# Charger.net
KiCad netlist of a schematic drawn in EAGLE
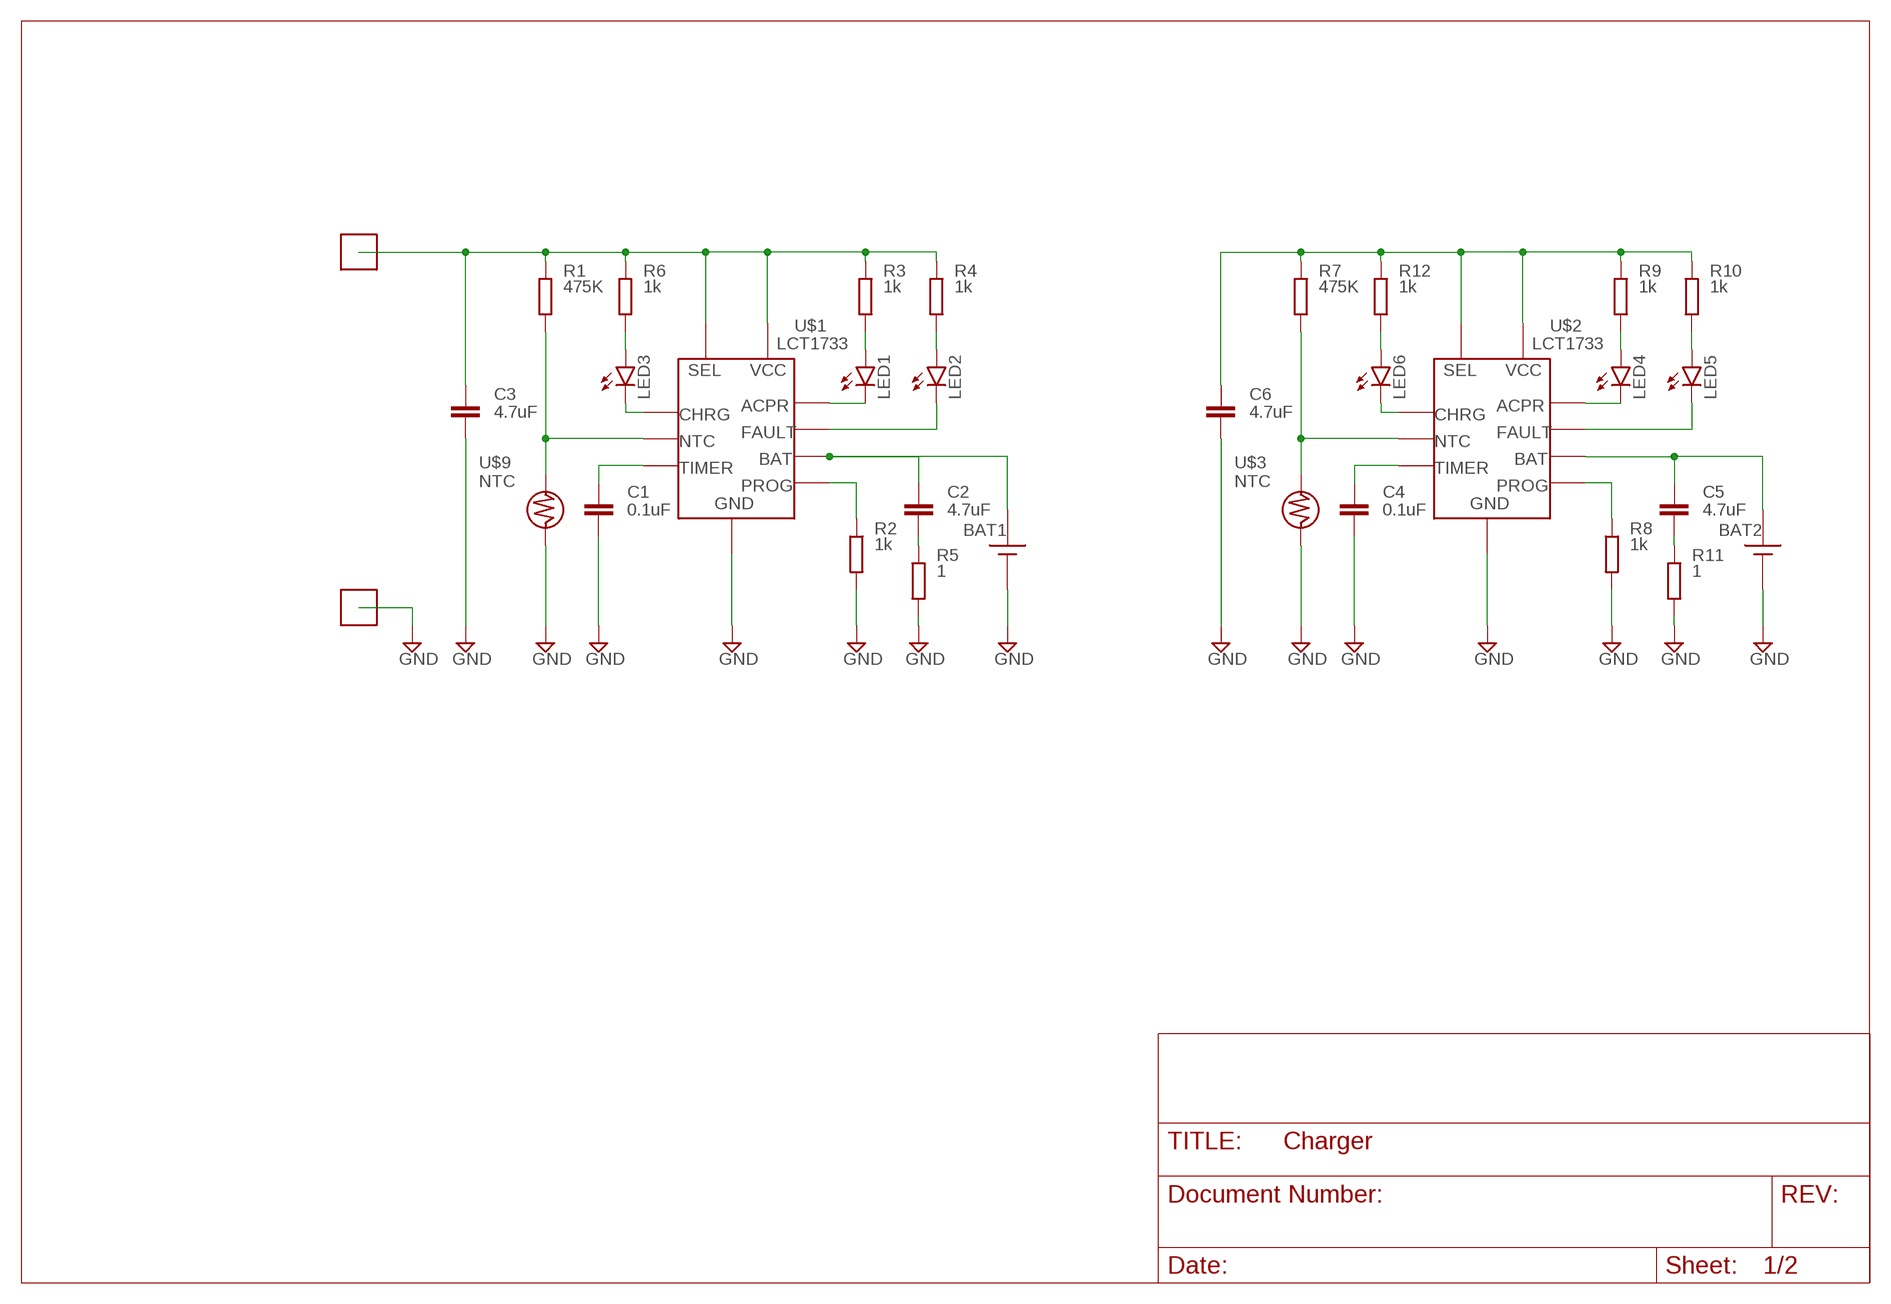
[diagram p0: schematic, sheet 1]
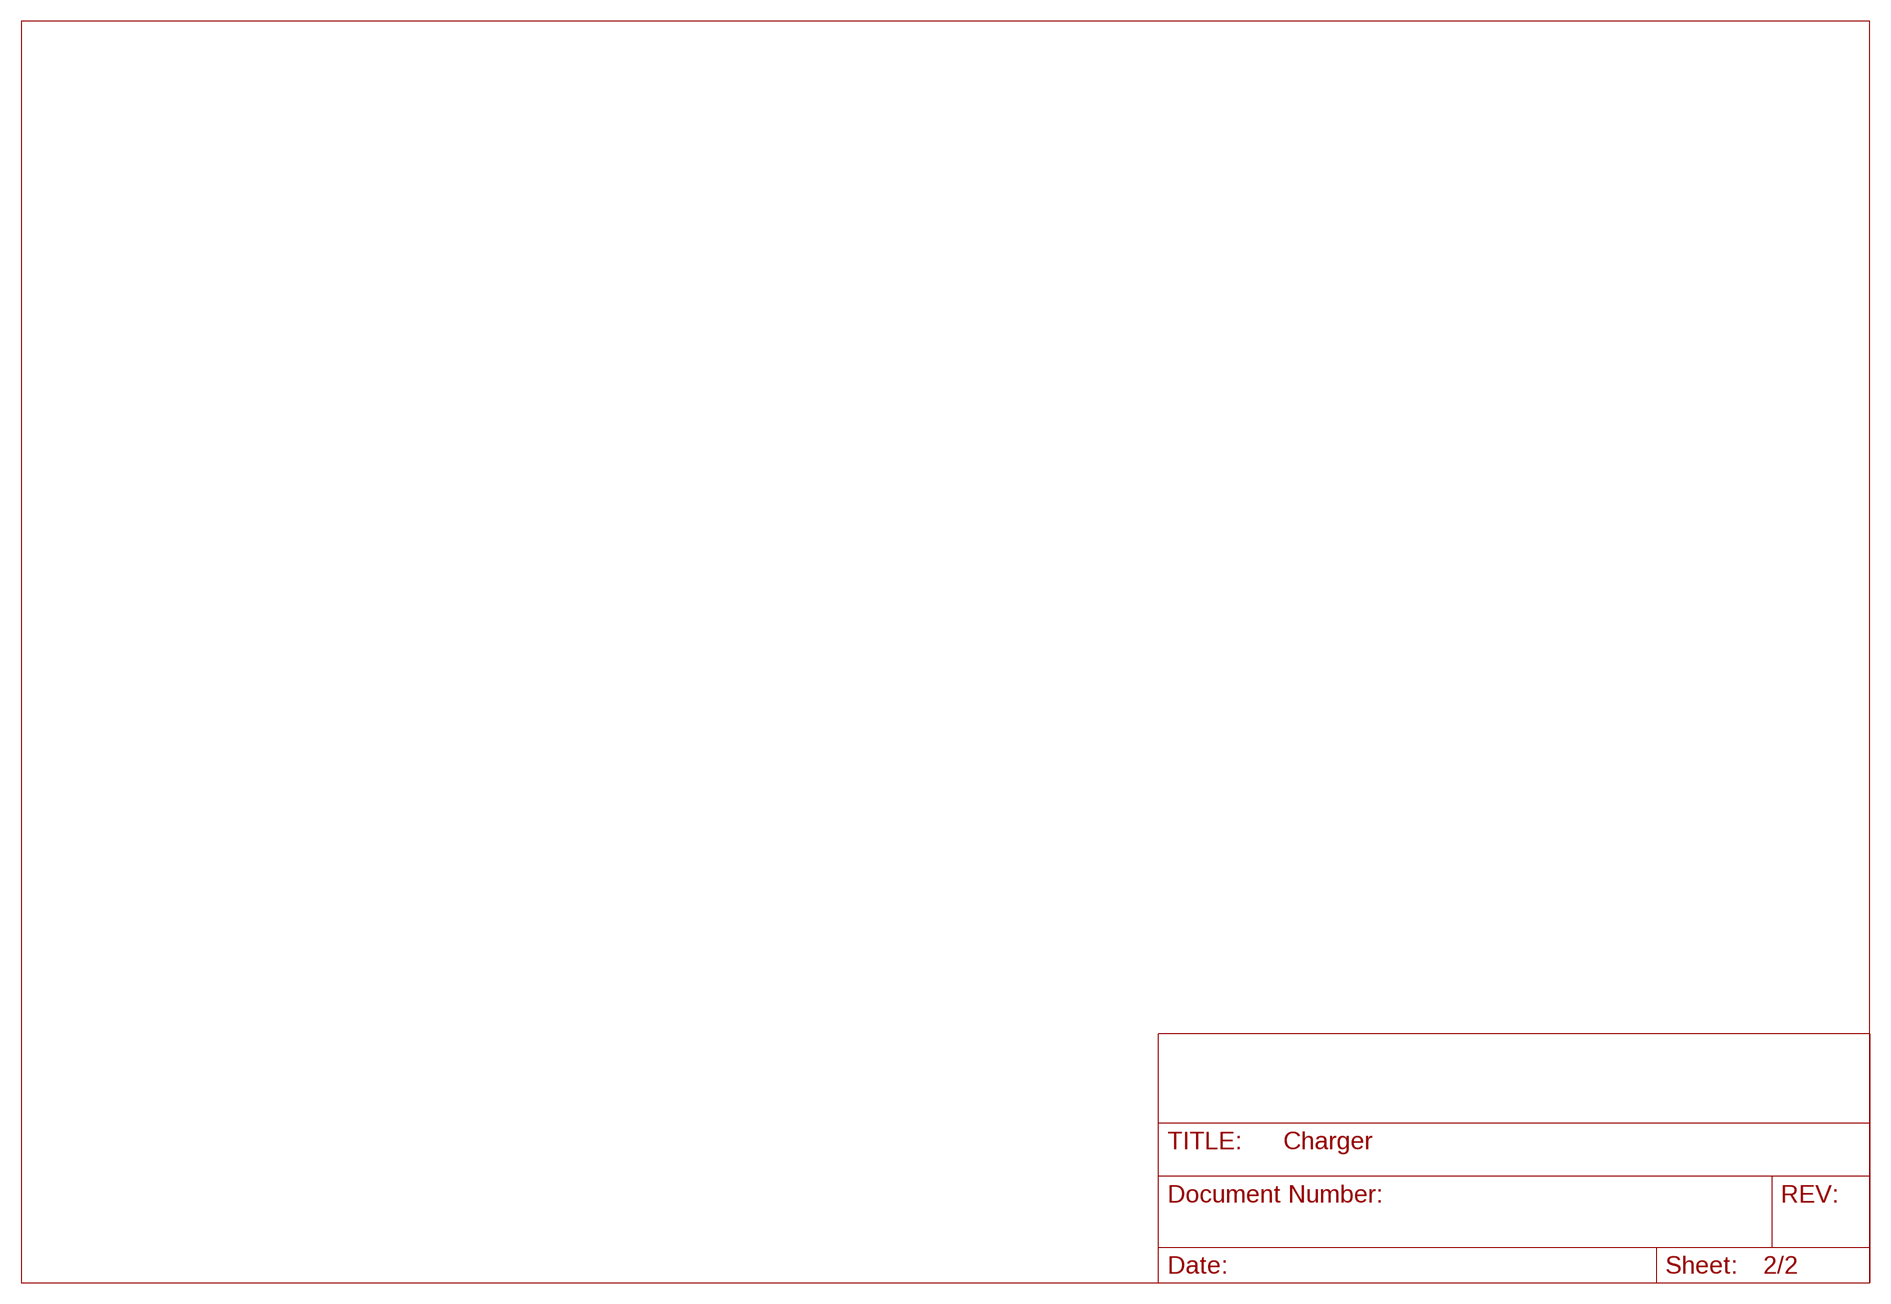
[diagram p1: schematic, sheet 2]

(export (version "E")
  (design (tool "Eeschema 10.0.6"))
  (components
    (comp (ref "BAT1")
      (value "BATBAT")
      (footprint "eagle-import:BAT2")
      (libsource (lib "eagle-import") (part "BATBAT"))
    )
    (comp (ref "BAT2")
      (value "BAT")
      (footprint "eagle-import:BAT")
      (libsource (lib "eagle-import") (part "BAT"))
    )
    (comp (ref "C1")
      (value "0.1uF")
      (footprint "eagle-import:C0603")
      (libsource (lib "eagle-import") (part "C-EUC0603"))
    )
    (comp (ref "C2")
      (value "4.7uF")
      (footprint "eagle-import:C0603")
      (libsource (lib "eagle-import") (part "C-EUC0603"))
    )
    (comp (ref "C3")
      (value "4.7uF")
      (footprint "eagle-import:C0603")
      (libsource (lib "eagle-import") (part "C-EUC0603"))
    )
    (comp (ref "C4")
      (value "0.1uF")
      (footprint "eagle-import:C0603")
      (libsource (lib "eagle-import") (part "C-EUC0603"))
    )
    (comp (ref "C5")
      (value "4.7uF")
      (footprint "eagle-import:C0603")
      (libsource (lib "eagle-import") (part "C-EUC0603"))
    )
    (comp (ref "C6")
      (value "4.7uF")
      (footprint "eagle-import:C0603")
      (libsource (lib "eagle-import") (part "C-EUC0603"))
    )
    (comp (ref "LED1")
      (value "LEDSML0603")
      (footprint "eagle-import:SML0603")
      (libsource (lib "eagle-import") (part "LEDSML0603"))
    )
    (comp (ref "LED2")
      (value "LEDSML0603")
      (footprint "eagle-import:SML0603")
      (libsource (lib "eagle-import") (part "LEDSML0603"))
    )
    (comp (ref "LED3")
      (value "LEDSML0603")
      (footprint "eagle-import:SML0603")
      (libsource (lib "eagle-import") (part "LEDSML0603"))
    )
    (comp (ref "LED4")
      (value "LEDSML0603")
      (footprint "eagle-import:SML0603")
      (libsource (lib "eagle-import") (part "LEDSML0603"))
    )
    (comp (ref "LED5")
      (value "LEDSML0603")
      (footprint "eagle-import:SML0603")
      (libsource (lib "eagle-import") (part "LEDSML0603"))
    )
    (comp (ref "LED6")
      (value "LEDSML0603")
      (footprint "eagle-import:SML0603")
      (libsource (lib "eagle-import") (part "LEDSML0603"))
    )
    (comp (ref "R1")
      (value "475K")
      (footprint "eagle-import:R0603")
      (libsource (lib "eagle-import") (part "R-EU_R0603"))
    )
    (comp (ref "R2")
      (value "1k")
      (footprint "eagle-import:R0603")
      (libsource (lib "eagle-import") (part "R-EU_R0603"))
    )
    (comp (ref "R3")
      (value "1k")
      (footprint "eagle-import:R0603")
      (libsource (lib "eagle-import") (part "R-EU_R0603"))
    )
    (comp (ref "R4")
      (value "1k")
      (footprint "eagle-import:R0603")
      (libsource (lib "eagle-import") (part "R-EU_R0603"))
    )
    (comp (ref "R5")
      (value "1")
      (footprint "eagle-import:R0603")
      (libsource (lib "eagle-import") (part "R-EU_R0603"))
    )
    (comp (ref "R6")
      (value "1k")
      (footprint "eagle-import:R0603")
      (libsource (lib "eagle-import") (part "R-EU_R0603"))
    )
    (comp (ref "R7")
      (value "475K")
      (footprint "eagle-import:R0603")
      (libsource (lib "eagle-import") (part "R-EU_R0603"))
    )
    (comp (ref "R8")
      (value "1k")
      (footprint "eagle-import:R0603")
      (libsource (lib "eagle-import") (part "R-EU_R0603"))
    )
    (comp (ref "R9")
      (value "1k")
      (footprint "eagle-import:R0603")
      (libsource (lib "eagle-import") (part "R-EU_R0603"))
    )
    (comp (ref "R10")
      (value "1k")
      (footprint "eagle-import:R0603")
      (libsource (lib "eagle-import") (part "R-EU_R0603"))
    )
    (comp (ref "R11")
      (value "1")
      (footprint "eagle-import:R0603")
      (libsource (lib "eagle-import") (part "R-EU_R0603"))
    )
    (comp (ref "R12")
      (value "1k")
      (footprint "eagle-import:R0603")
      (libsource (lib "eagle-import") (part "R-EU_R0603"))
    )
    (comp (ref "U$1")
      (value "LCT1733")
      (footprint "eagle-import:MSOP-10_MSE")
      (libsource (lib "eagle-import") (part "LCT1733"))
    )
    (comp (ref "U$2")
      (value "LCT1733")
      (footprint "eagle-import:MSOP-10_MSE")
      (libsource (lib "eagle-import") (part "LCT1733"))
    )
    (comp (ref "U$3")
      (value "NTC")
      (footprint "eagle-import:C0603")
      (libsource (lib "eagle-import") (part "NTC"))
    )
    (comp (ref "U$4")
      (value "CONNECTOR")
      (footprint "eagle-import:VCC")
      (libsource (lib "eagle-import") (part "CONNECTOR"))
    )
    (comp (ref "U$5")
      (value "CONNECTOR")
      (footprint "eagle-import:VCC")
      (libsource (lib "eagle-import") (part "CONNECTOR"))
    )
    (comp (ref "U$9")
      (value "NTC")
      (footprint "eagle-import:C0603")
      (libsource (lib "eagle-import") (part "NTC"))
    )
  )
  (nets
    (net (code "1") (name "GND") (class "Default")
      (node (ref "BAT1") (pin "P$2") (pinfunction "-_P$2") (pintype "bidirectional"))
      (node (ref "BAT2") (pin "P$2") (pinfunction "-_P$2") (pintype "bidirectional"))
      (node (ref "C1") (pin "2") (pinfunction "2_2") (pintype "passive"))
      (node (ref "C3") (pin "2") (pinfunction "2_2") (pintype "passive"))
      (node (ref "C4") (pin "2") (pinfunction "2_2") (pintype "passive"))
      (node (ref "C6") (pin "2") (pinfunction "2_2") (pintype "passive"))
      (node (ref "R11") (pin "2") (pinfunction "2_2") (pintype "passive"))
      (node (ref "R2") (pin "2") (pinfunction "2_2") (pintype "passive"))
      (node (ref "R5") (pin "2") (pinfunction "2_2") (pintype "passive"))
      (node (ref "R8") (pin "2") (pinfunction "2_2") (pintype "passive"))
      (node (ref "U$1") (pin "11") (pinfunction "GND_11") (pintype "bidirectional"))
      (node (ref "U$1") (pin "5") (pinfunction "GND_5") (pintype "bidirectional"))
      (node (ref "U$2") (pin "11") (pinfunction "GND_11") (pintype "bidirectional"))
      (node (ref "U$2") (pin "5") (pinfunction "GND_5") (pintype "bidirectional"))
      (node (ref "U$3") (pin "2") (pinfunction "P$2_2") (pintype "bidirectional"))
      (node (ref "U$5") (pin "P$1") (pinfunction "P$1_P$1") (pintype "bidirectional"))
      (node (ref "U$9") (pin "2") (pinfunction "P$2_2") (pintype "bidirectional"))
    )
    (net (code "2") (name "Net-(BAT1-+)") (class "Default")
      (node (ref "BAT1") (pin "P$1") (pinfunction "+_P$1") (pintype "bidirectional"))
      (node (ref "C2") (pin "1") (pinfunction "1_1") (pintype "passive"))
      (node (ref "U$1") (pin "9") (pinfunction "BAT_9") (pintype "bidirectional"))
    )
    (net (code "3") (name "Net-(BAT2-+)") (class "Default")
      (node (ref "BAT2") (pin "P$1") (pinfunction "+_P$1") (pintype "bidirectional"))
      (node (ref "C5") (pin "1") (pinfunction "1_1") (pintype "passive"))
      (node (ref "U$2") (pin "9") (pinfunction "BAT_9") (pintype "bidirectional"))
    )
    (net (code "4") (name "Net-(C2-Pad2)") (class "Default")
      (node (ref "C2") (pin "2") (pinfunction "2_2") (pintype "passive"))
      (node (ref "R5") (pin "1") (pinfunction "1_1") (pintype "passive"))
    )
    (net (code "5") (name "Net-(C5-Pad2)") (class "Default")
      (node (ref "C5") (pin "2") (pinfunction "2_2") (pintype "passive"))
      (node (ref "R11") (pin "1") (pinfunction "1_1") (pintype "passive"))
    )
    (net (code "6") (name "Net-(LED1-PadA)") (class "Default")
      (node (ref "LED1") (pin "A") (pinfunction "A_A") (pintype "passive"))
      (node (ref "R3") (pin "2") (pinfunction "2_2") (pintype "passive"))
    )
    (net (code "7") (name "Net-(LED2-PadA)") (class "Default")
      (node (ref "LED2") (pin "A") (pinfunction "A_A") (pintype "passive"))
      (node (ref "R4") (pin "2") (pinfunction "2_2") (pintype "passive"))
    )
    (net (code "8") (name "Net-(LED3-PadA)") (class "Default")
      (node (ref "LED3") (pin "A") (pinfunction "A_A") (pintype "passive"))
      (node (ref "R6") (pin "2") (pinfunction "2_2") (pintype "passive"))
    )
    (net (code "9") (name "Net-(LED4-PadA)") (class "Default")
      (node (ref "LED4") (pin "A") (pinfunction "A_A") (pintype "passive"))
      (node (ref "R9") (pin "2") (pinfunction "2_2") (pintype "passive"))
    )
    (net (code "10") (name "Net-(LED5-PadA)") (class "Default")
      (node (ref "LED5") (pin "A") (pinfunction "A_A") (pintype "passive"))
      (node (ref "R10") (pin "2") (pinfunction "2_2") (pintype "passive"))
    )
    (net (code "11") (name "Net-(LED6-PadA)") (class "Default")
      (node (ref "LED6") (pin "A") (pinfunction "A_A") (pintype "passive"))
      (node (ref "R12") (pin "2") (pinfunction "2_2") (pintype "passive"))
    )
    (net (code "12") (name "Net-(U$1-ACPR)") (class "Default")
      (node (ref "LED1") (pin "C") (pinfunction "C_C") (pintype "passive"))
      (node (ref "U$1") (pin "10") (pinfunction "ACPR_10") (pintype "bidirectional"))
    )
    (net (code "13") (name "Net-(U$1-CHRG)") (class "Default")
      (node (ref "LED3") (pin "C") (pinfunction "C_C") (pintype "passive"))
      (node (ref "U$1") (pin "1") (pinfunction "CHRG_1") (pintype "bidirectional"))
    )
    (net (code "14") (name "Net-(U$1-FAULT)") (class "Default")
      (node (ref "LED2") (pin "C") (pinfunction "C_C") (pintype "passive"))
      (node (ref "U$1") (pin "3") (pinfunction "FAULT_3") (pintype "bidirectional"))
    )
    (net (code "15") (name "Net-(U$1-NTC)") (class "Default")
      (node (ref "R1") (pin "2") (pinfunction "2_2") (pintype "passive"))
      (node (ref "U$1") (pin "6") (pinfunction "NTC_6") (pintype "bidirectional"))
      (node (ref "U$9") (pin "1") (pinfunction "P$1_1") (pintype "bidirectional"))
    )
    (net (code "16") (name "Net-(U$1-PROG)") (class "Default")
      (node (ref "R2") (pin "1") (pinfunction "1_1") (pintype "passive"))
      (node (ref "U$1") (pin "7") (pinfunction "PROG_7") (pintype "bidirectional"))
    )
    (net (code "17") (name "Net-(U$1-SEL)") (class "Default")
      (node (ref "C3") (pin "1") (pinfunction "1_1") (pintype "passive"))
      (node (ref "R1") (pin "1") (pinfunction "1_1") (pintype "passive"))
      (node (ref "R3") (pin "1") (pinfunction "1_1") (pintype "passive"))
      (node (ref "R4") (pin "1") (pinfunction "1_1") (pintype "passive"))
      (node (ref "R6") (pin "1") (pinfunction "1_1") (pintype "passive"))
      (node (ref "U$1") (pin "2") (pinfunction "VCC_2") (pintype "bidirectional"))
      (node (ref "U$1") (pin "8") (pinfunction "SEL_8") (pintype "bidirectional"))
      (node (ref "U$4") (pin "P$1") (pinfunction "P$1_P$1") (pintype "bidirectional"))
    )
    (net (code "18") (name "Net-(U$1-TIM)") (class "Default")
      (node (ref "C1") (pin "1") (pinfunction "1_1") (pintype "passive"))
      (node (ref "U$1") (pin "4") (pinfunction "TIM_4") (pintype "bidirectional"))
    )
    (net (code "19") (name "Net-(U$2-ACPR)") (class "Default")
      (node (ref "LED4") (pin "C") (pinfunction "C_C") (pintype "passive"))
      (node (ref "U$2") (pin "10") (pinfunction "ACPR_10") (pintype "bidirectional"))
    )
    (net (code "20") (name "Net-(U$2-CHRG)") (class "Default")
      (node (ref "LED6") (pin "C") (pinfunction "C_C") (pintype "passive"))
      (node (ref "U$2") (pin "1") (pinfunction "CHRG_1") (pintype "bidirectional"))
    )
    (net (code "21") (name "Net-(U$2-FAULT)") (class "Default")
      (node (ref "LED5") (pin "C") (pinfunction "C_C") (pintype "passive"))
      (node (ref "U$2") (pin "3") (pinfunction "FAULT_3") (pintype "bidirectional"))
    )
    (net (code "22") (name "Net-(U$2-NTC)") (class "Default")
      (node (ref "R7") (pin "2") (pinfunction "2_2") (pintype "passive"))
      (node (ref "U$2") (pin "6") (pinfunction "NTC_6") (pintype "bidirectional"))
      (node (ref "U$3") (pin "1") (pinfunction "P$1_1") (pintype "bidirectional"))
    )
    (net (code "23") (name "Net-(U$2-PROG)") (class "Default")
      (node (ref "R8") (pin "1") (pinfunction "1_1") (pintype "passive"))
      (node (ref "U$2") (pin "7") (pinfunction "PROG_7") (pintype "bidirectional"))
    )
    (net (code "24") (name "Net-(U$2-SEL)") (class "Default")
      (node (ref "C6") (pin "1") (pinfunction "1_1") (pintype "passive"))
      (node (ref "R10") (pin "1") (pinfunction "1_1") (pintype "passive"))
      (node (ref "R12") (pin "1") (pinfunction "1_1") (pintype "passive"))
      (node (ref "R7") (pin "1") (pinfunction "1_1") (pintype "passive"))
      (node (ref "R9") (pin "1") (pinfunction "1_1") (pintype "passive"))
      (node (ref "U$2") (pin "2") (pinfunction "VCC_2") (pintype "bidirectional"))
      (node (ref "U$2") (pin "8") (pinfunction "SEL_8") (pintype "bidirectional"))
    )
    (net (code "25") (name "Net-(U$2-TIM)") (class "Default")
      (node (ref "C4") (pin "1") (pinfunction "1_1") (pintype "passive"))
      (node (ref "U$2") (pin "4") (pinfunction "TIM_4") (pintype "bidirectional"))
    )
  )
)
